# 20260317.net
KiCad netlist of a schematic drawn in EasyEDA Pro
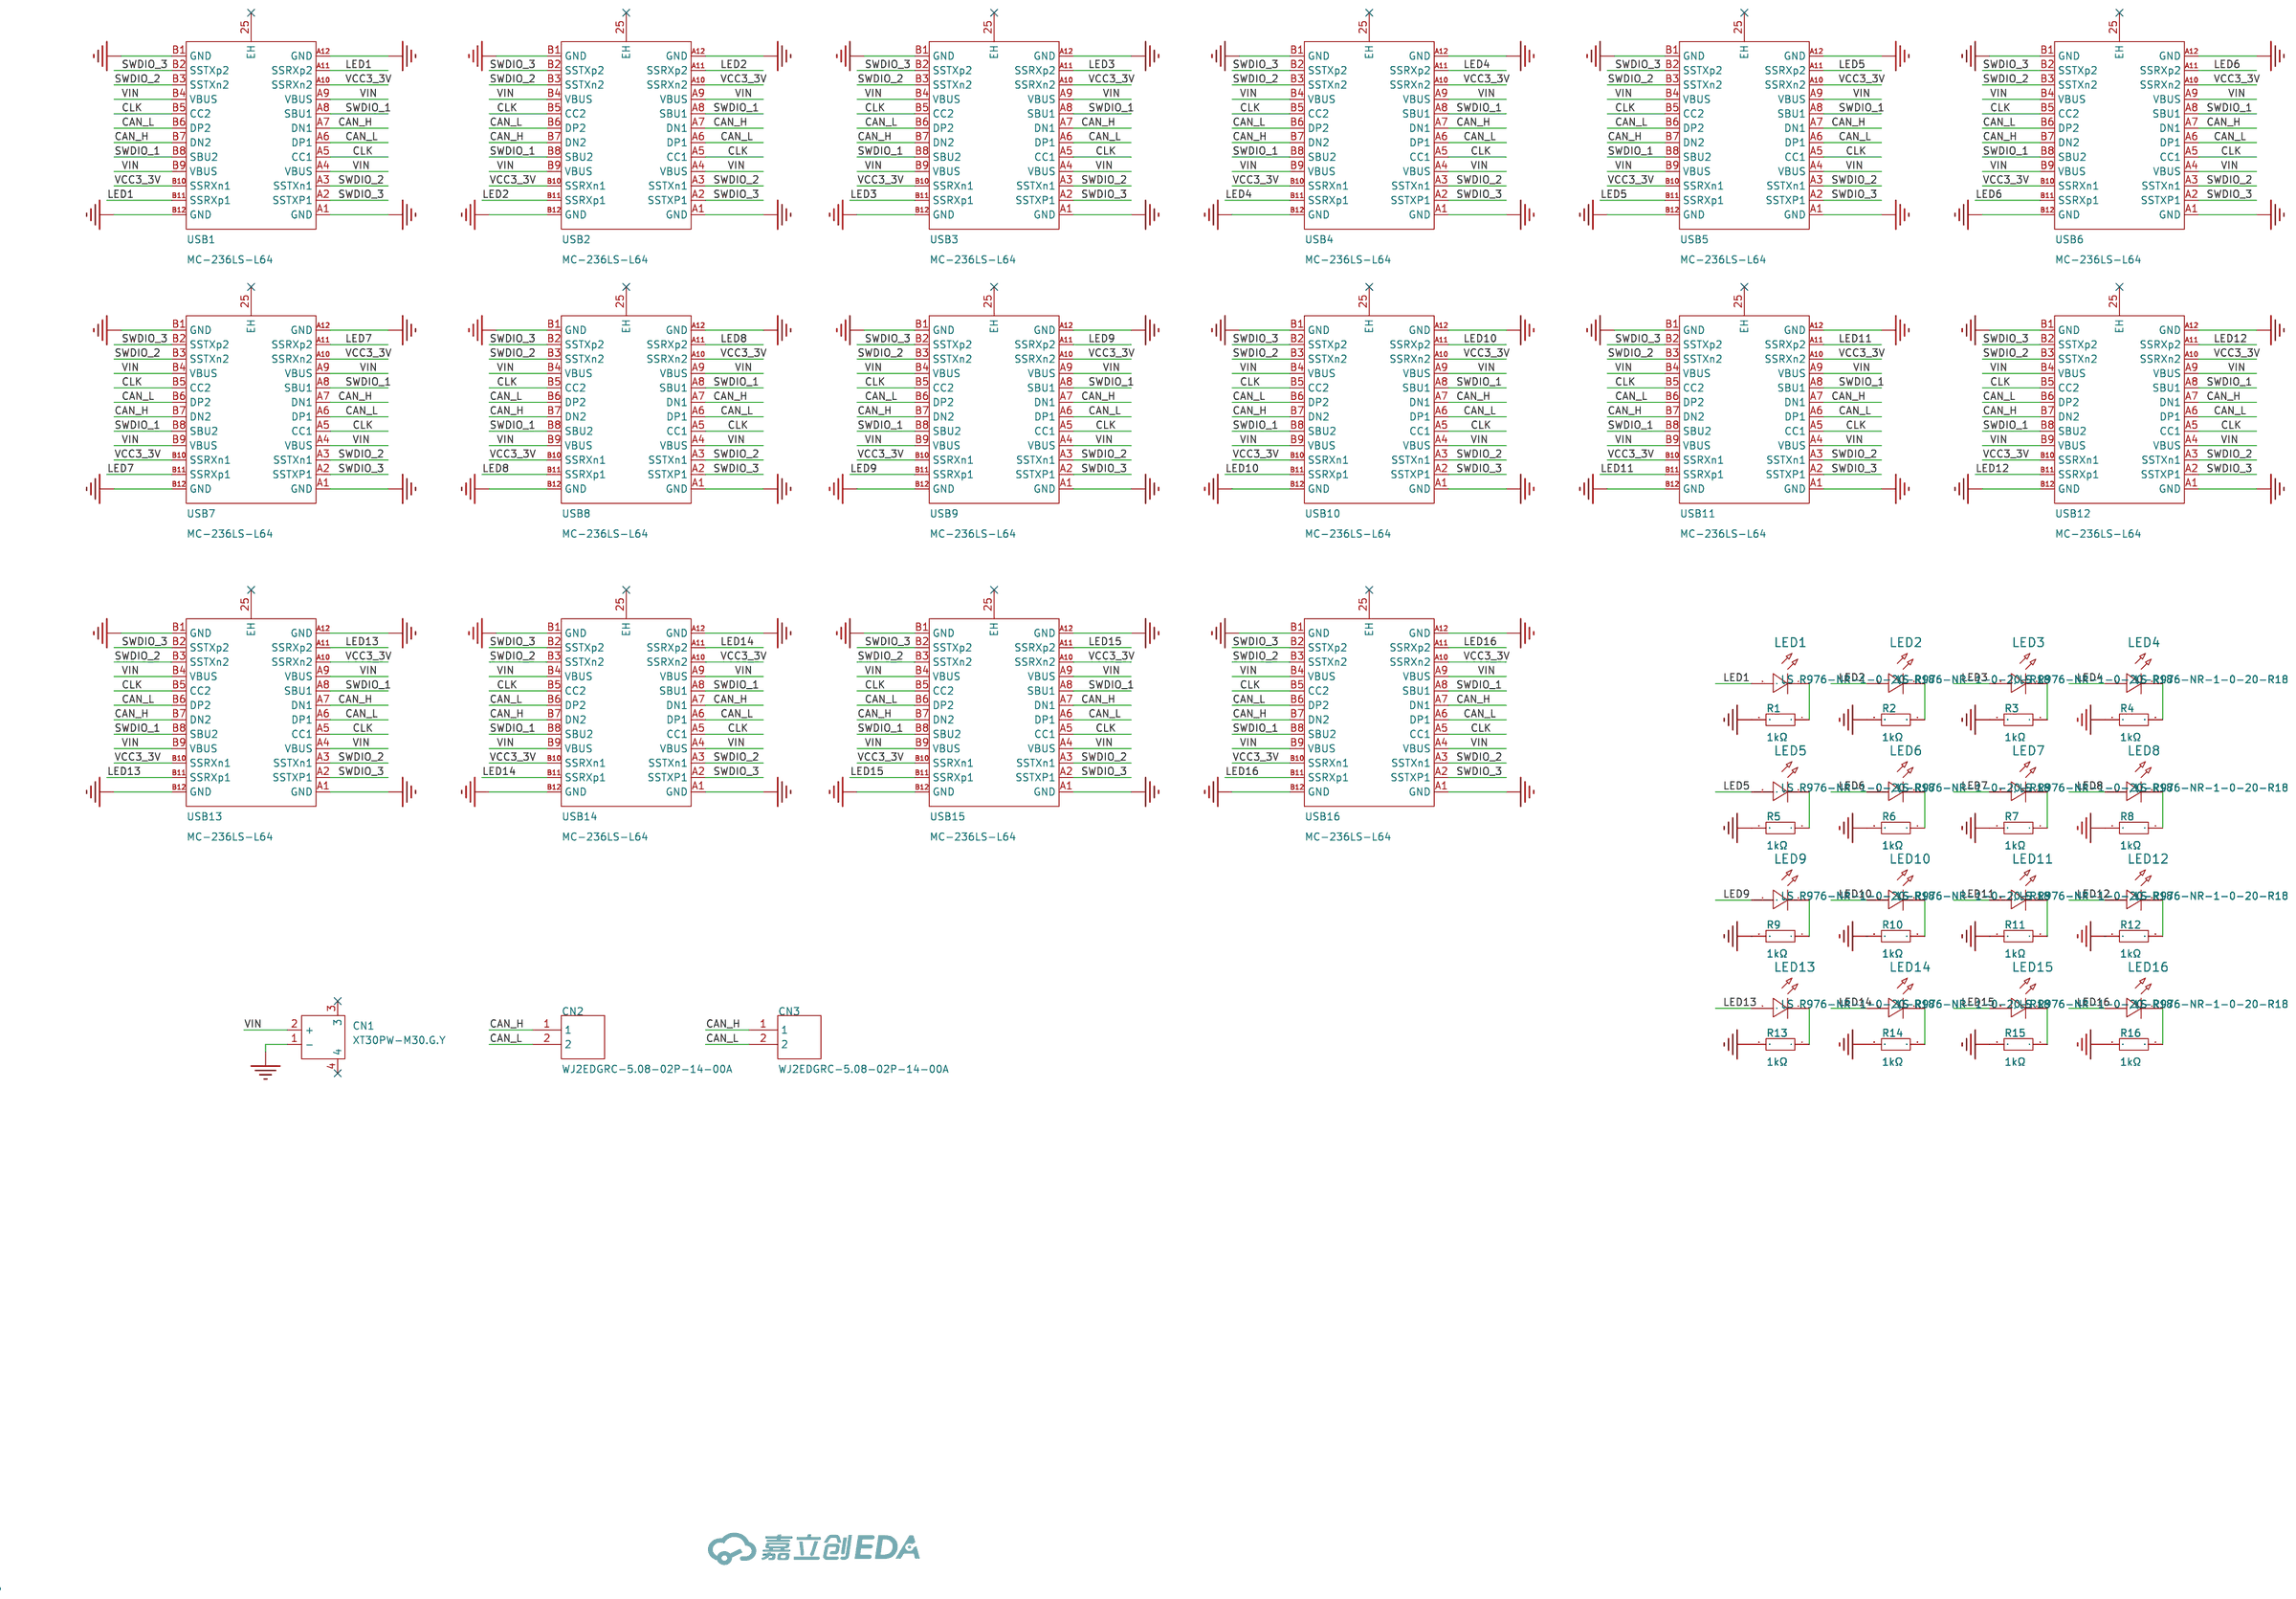
[diagram p0: schematic sheet]

(export (version "E")
  (design (tool "Eeschema 10.0.6"))
  (components
    (comp (ref "CN1")
      (value "XT30PW-M30.G.Y")
      (footprint "easyedapro:CONN-TH_XT30PW-M")
      (description "类别:-;类型1:-;")
      (fields (field (name "Manufacturer") "AMASS(艾迈斯)"))
      (libsource (lib "easyedapro") (part "XT30PW-M"))
    )
    (comp (ref "CN2")
      (value "WJ2EDGRC-5.08-02P-14-00A")
      (footprint "easyedapro:CONN-TH_2P-P5.08_WJ2EDGRC-5.08-2P")
      (fields (field (name "Manufacturer") "KANGNEX(康奈克斯电气)"))
      (libsource (lib "easyedapro") (part "WJ2EDGRC-5.08-2P"))
    )
    (comp (ref "CN3")
      (value "WJ2EDGRC-5.08-02P-14-00A")
      (footprint "easyedapro:CONN-TH_2P-P5.08_WJ2EDGRC-5.08-2P")
      (fields (field (name "Manufacturer") "KANGNEX(康奈克斯电气)"))
      (libsource (lib "easyedapro") (part "WJ2EDGRC-5.08-2P"))
    )
    (comp (ref "LED1")
      (value "LS R976-NR-1-0-20-R18")
      (footprint "easyedapro:LED_0805")
      (fields (field (name "Manufacturer") "OSRAM(欧司朗)"))
      (libsource (lib "easyedapro") (part "LED_R"))
    )
    (comp (ref "LED2")
      (value "LS R976-NR-1-0-20-R18")
      (footprint "easyedapro:LED_0805")
      (fields (field (name "Manufacturer") "OSRAM(欧司朗)"))
      (libsource (lib "easyedapro") (part "LED_R"))
    )
    (comp (ref "LED3")
      (value "LS R976-NR-1-0-20-R18")
      (footprint "easyedapro:LED_0805")
      (fields (field (name "Manufacturer") "OSRAM(欧司朗)"))
      (libsource (lib "easyedapro") (part "LED_R"))
    )
    (comp (ref "LED4")
      (value "LS R976-NR-1-0-20-R18")
      (footprint "easyedapro:LED_0805")
      (fields (field (name "Manufacturer") "OSRAM(欧司朗)"))
      (libsource (lib "easyedapro") (part "LED_R"))
    )
    (comp (ref "LED5")
      (value "LS R976-NR-1-0-20-R18")
      (footprint "easyedapro:LED_0805")
      (fields (field (name "Manufacturer") "OSRAM(欧司朗)"))
      (libsource (lib "easyedapro") (part "LED_R"))
    )
    (comp (ref "LED6")
      (value "LS R976-NR-1-0-20-R18")
      (footprint "easyedapro:LED_0805")
      (fields (field (name "Manufacturer") "OSRAM(欧司朗)"))
      (libsource (lib "easyedapro") (part "LED_R"))
    )
    (comp (ref "LED7")
      (value "LS R976-NR-1-0-20-R18")
      (footprint "easyedapro:LED_0805")
      (fields (field (name "Manufacturer") "OSRAM(欧司朗)"))
      (libsource (lib "easyedapro") (part "LED_R"))
    )
    (comp (ref "LED8")
      (value "LS R976-NR-1-0-20-R18")
      (footprint "easyedapro:LED_0805")
      (fields (field (name "Manufacturer") "OSRAM(欧司朗)"))
      (libsource (lib "easyedapro") (part "LED_R"))
    )
    (comp (ref "LED9")
      (value "LS R976-NR-1-0-20-R18")
      (footprint "easyedapro:LED_0805")
      (fields (field (name "Manufacturer") "OSRAM(欧司朗)"))
      (libsource (lib "easyedapro") (part "LED_R"))
    )
    (comp (ref "LED10")
      (value "LS R976-NR-1-0-20-R18")
      (footprint "easyedapro:LED_0805")
      (fields (field (name "Manufacturer") "OSRAM(欧司朗)"))
      (libsource (lib "easyedapro") (part "LED_R"))
    )
    (comp (ref "LED11")
      (value "LS R976-NR-1-0-20-R18")
      (footprint "easyedapro:LED_0805")
      (fields (field (name "Manufacturer") "OSRAM(欧司朗)"))
      (libsource (lib "easyedapro") (part "LED_R"))
    )
    (comp (ref "LED12")
      (value "LS R976-NR-1-0-20-R18")
      (footprint "easyedapro:LED_0805")
      (fields (field (name "Manufacturer") "OSRAM(欧司朗)"))
      (libsource (lib "easyedapro") (part "LED_R"))
    )
    (comp (ref "LED13")
      (value "LS R976-NR-1-0-20-R18")
      (footprint "easyedapro:LED_0805")
      (fields (field (name "Manufacturer") "OSRAM(欧司朗)"))
      (libsource (lib "easyedapro") (part "LED_R"))
    )
    (comp (ref "LED14")
      (value "LS R976-NR-1-0-20-R18")
      (footprint "easyedapro:LED_0805")
      (fields (field (name "Manufacturer") "OSRAM(欧司朗)"))
      (libsource (lib "easyedapro") (part "LED_R"))
    )
    (comp (ref "LED15")
      (value "LS R976-NR-1-0-20-R18")
      (footprint "easyedapro:LED_0805")
      (fields (field (name "Manufacturer") "OSRAM(欧司朗)"))
      (libsource (lib "easyedapro") (part "LED_R"))
    )
    (comp (ref "LED16")
      (value "LS R976-NR-1-0-20-R18")
      (footprint "easyedapro:LED_0805")
      (fields (field (name "Manufacturer") "OSRAM(欧司朗)"))
      (libsource (lib "easyedapro") (part "LED_R"))
    )
    (comp (ref "R1")
      (value "1kΩ")
      (footprint "easyedapro:R0805")
      (fields
        (field (name "Manufacturer Part") "0805W8F1001T5E")
        (field (name "Manufacturer") "UNI-ROYAL(厚声)")
      )
      (libsource (lib "easyedapro") (part "电阻"))
    )
    (comp (ref "R2")
      (value "1kΩ")
      (footprint "easyedapro:R0805")
      (fields
        (field (name "Manufacturer Part") "0805W8F1001T5E")
        (field (name "Manufacturer") "UNI-ROYAL(厚声)")
      )
      (libsource (lib "easyedapro") (part "电阻"))
    )
    (comp (ref "R3")
      (value "1kΩ")
      (footprint "easyedapro:R0805")
      (fields
        (field (name "Manufacturer Part") "0805W8F1001T5E")
        (field (name "Manufacturer") "UNI-ROYAL(厚声)")
      )
      (libsource (lib "easyedapro") (part "电阻"))
    )
    (comp (ref "R4")
      (value "1kΩ")
      (footprint "easyedapro:R0805")
      (fields
        (field (name "Manufacturer Part") "0805W8F1001T5E")
        (field (name "Manufacturer") "UNI-ROYAL(厚声)")
      )
      (libsource (lib "easyedapro") (part "电阻"))
    )
    (comp (ref "R5")
      (value "1kΩ")
      (footprint "easyedapro:R0805")
      (fields
        (field (name "Manufacturer Part") "0805W8F1001T5E")
        (field (name "Manufacturer") "UNI-ROYAL(厚声)")
      )
      (libsource (lib "easyedapro") (part "电阻"))
    )
    (comp (ref "R6")
      (value "1kΩ")
      (footprint "easyedapro:R0805")
      (fields
        (field (name "Manufacturer Part") "0805W8F1001T5E")
        (field (name "Manufacturer") "UNI-ROYAL(厚声)")
      )
      (libsource (lib "easyedapro") (part "电阻"))
    )
    (comp (ref "R7")
      (value "1kΩ")
      (footprint "easyedapro:R0805")
      (fields
        (field (name "Manufacturer Part") "0805W8F1001T5E")
        (field (name "Manufacturer") "UNI-ROYAL(厚声)")
      )
      (libsource (lib "easyedapro") (part "电阻"))
    )
    (comp (ref "R8")
      (value "1kΩ")
      (footprint "easyedapro:R0805")
      (fields
        (field (name "Manufacturer Part") "0805W8F1001T5E")
        (field (name "Manufacturer") "UNI-ROYAL(厚声)")
      )
      (libsource (lib "easyedapro") (part "电阻"))
    )
    (comp (ref "R9")
      (value "1kΩ")
      (footprint "easyedapro:R0805")
      (fields
        (field (name "Manufacturer Part") "0805W8F1001T5E")
        (field (name "Manufacturer") "UNI-ROYAL(厚声)")
      )
      (libsource (lib "easyedapro") (part "电阻"))
    )
    (comp (ref "R10")
      (value "1kΩ")
      (footprint "easyedapro:R0805")
      (fields
        (field (name "Manufacturer Part") "0805W8F1001T5E")
        (field (name "Manufacturer") "UNI-ROYAL(厚声)")
      )
      (libsource (lib "easyedapro") (part "电阻"))
    )
    (comp (ref "R11")
      (value "1kΩ")
      (footprint "easyedapro:R0805")
      (fields
        (field (name "Manufacturer Part") "0805W8F1001T5E")
        (field (name "Manufacturer") "UNI-ROYAL(厚声)")
      )
      (libsource (lib "easyedapro") (part "电阻"))
    )
    (comp (ref "R12")
      (value "1kΩ")
      (footprint "easyedapro:R0805")
      (fields
        (field (name "Manufacturer Part") "0805W8F1001T5E")
        (field (name "Manufacturer") "UNI-ROYAL(厚声)")
      )
      (libsource (lib "easyedapro") (part "电阻"))
    )
    (comp (ref "R13")
      (value "1kΩ")
      (footprint "easyedapro:R0805")
      (fields
        (field (name "Manufacturer Part") "0805W8F1001T5E")
        (field (name "Manufacturer") "UNI-ROYAL(厚声)")
      )
      (libsource (lib "easyedapro") (part "电阻"))
    )
    (comp (ref "R14")
      (value "1kΩ")
      (footprint "easyedapro:R0805")
      (fields
        (field (name "Manufacturer Part") "0805W8F1001T5E")
        (field (name "Manufacturer") "UNI-ROYAL(厚声)")
      )
      (libsource (lib "easyedapro") (part "电阻"))
    )
    (comp (ref "R15")
      (value "1kΩ")
      (footprint "easyedapro:R0805")
      (fields
        (field (name "Manufacturer Part") "0805W8F1001T5E")
        (field (name "Manufacturer") "UNI-ROYAL(厚声)")
      )
      (libsource (lib "easyedapro") (part "电阻"))
    )
    (comp (ref "R16")
      (value "1kΩ")
      (footprint "easyedapro:R0805")
      (fields
        (field (name "Manufacturer Part") "0805W8F1001T5E")
        (field (name "Manufacturer") "UNI-ROYAL(厚声)")
      )
      (libsource (lib "easyedapro") (part "电阻"))
    )
    (comp (ref "USB1")
      (value "MC-236LS-L64")
      (footprint "easyedapro:TYPE-C-USB-SMD_TYPE-C-31-M-06")
      (description "连接器类型:Type-C;协议标准:USB 3.1;公母:母;安装方式:立贴;触点数量:24P;端口数量:1;额定电流 - 电源:5A;工作温度:-25°C~+85°C;")
      (fields (field (name "Manufacturer") "HANBO(汉博)"))
      (libsource (lib "easyedapro") (part "MC-236LS-L64"))
    )
    (comp (ref "USB2")
      (value "MC-236LS-L64")
      (footprint "easyedapro:TYPE-C-USB-SMD_TYPE-C-31-M-06")
      (description "连接器类型:Type-C;协议标准:USB 3.1;公母:母;安装方式:立贴;触点数量:24P;端口数量:1;额定电流 - 电源:5A;工作温度:-25°C~+85°C;")
      (fields (field (name "Manufacturer") "HANBO(汉博)"))
      (libsource (lib "easyedapro") (part "MC-236LS-L64"))
    )
    (comp (ref "USB3")
      (value "MC-236LS-L64")
      (footprint "easyedapro:TYPE-C-USB-SMD_TYPE-C-31-M-06")
      (description "连接器类型:Type-C;协议标准:USB 3.1;公母:母;安装方式:立贴;触点数量:24P;端口数量:1;额定电流 - 电源:5A;工作温度:-25°C~+85°C;")
      (fields (field (name "Manufacturer") "HANBO(汉博)"))
      (libsource (lib "easyedapro") (part "MC-236LS-L64"))
    )
    (comp (ref "USB4")
      (value "MC-236LS-L64")
      (footprint "easyedapro:TYPE-C-USB-SMD_TYPE-C-31-M-06")
      (description "连接器类型:Type-C;协议标准:USB 3.1;公母:母;安装方式:立贴;触点数量:24P;端口数量:1;额定电流 - 电源:5A;工作温度:-25°C~+85°C;")
      (fields (field (name "Manufacturer") "HANBO(汉博)"))
      (libsource (lib "easyedapro") (part "MC-236LS-L64"))
    )
    (comp (ref "USB5")
      (value "MC-236LS-L64")
      (footprint "easyedapro:TYPE-C-USB-SMD_TYPE-C-31-M-06")
      (description "连接器类型:Type-C;协议标准:USB 3.1;公母:母;安装方式:立贴;触点数量:24P;端口数量:1;额定电流 - 电源:5A;工作温度:-25°C~+85°C;")
      (fields (field (name "Manufacturer") "HANBO(汉博)"))
      (libsource (lib "easyedapro") (part "MC-236LS-L64"))
    )
    (comp (ref "USB6")
      (value "MC-236LS-L64")
      (footprint "easyedapro:TYPE-C-USB-SMD_TYPE-C-31-M-06")
      (description "连接器类型:Type-C;协议标准:USB 3.1;公母:母;安装方式:立贴;触点数量:24P;端口数量:1;额定电流 - 电源:5A;工作温度:-25°C~+85°C;")
      (fields (field (name "Manufacturer") "HANBO(汉博)"))
      (libsource (lib "easyedapro") (part "MC-236LS-L64"))
    )
    (comp (ref "USB7")
      (value "MC-236LS-L64")
      (footprint "easyedapro:TYPE-C-USB-SMD_TYPE-C-31-M-06")
      (description "连接器类型:Type-C;协议标准:USB 3.1;公母:母;安装方式:立贴;触点数量:24P;端口数量:1;额定电流 - 电源:5A;工作温度:-25°C~+85°C;")
      (fields (field (name "Manufacturer") "HANBO(汉博)"))
      (libsource (lib "easyedapro") (part "MC-236LS-L64"))
    )
    (comp (ref "USB8")
      (value "MC-236LS-L64")
      (footprint "easyedapro:TYPE-C-USB-SMD_TYPE-C-31-M-06")
      (description "连接器类型:Type-C;协议标准:USB 3.1;公母:母;安装方式:立贴;触点数量:24P;端口数量:1;额定电流 - 电源:5A;工作温度:-25°C~+85°C;")
      (fields (field (name "Manufacturer") "HANBO(汉博)"))
      (libsource (lib "easyedapro") (part "MC-236LS-L64"))
    )
    (comp (ref "USB9")
      (value "MC-236LS-L64")
      (footprint "easyedapro:TYPE-C-USB-SMD_TYPE-C-31-M-06")
      (description "连接器类型:Type-C;协议标准:USB 3.1;公母:母;安装方式:立贴;触点数量:24P;端口数量:1;额定电流 - 电源:5A;工作温度:-25°C~+85°C;")
      (fields (field (name "Manufacturer") "HANBO(汉博)"))
      (libsource (lib "easyedapro") (part "MC-236LS-L64"))
    )
    (comp (ref "USB10")
      (value "MC-236LS-L64")
      (footprint "easyedapro:TYPE-C-USB-SMD_TYPE-C-31-M-06")
      (description "连接器类型:Type-C;协议标准:USB 3.1;公母:母;安装方式:立贴;触点数量:24P;端口数量:1;额定电流 - 电源:5A;工作温度:-25°C~+85°C;")
      (fields (field (name "Manufacturer") "HANBO(汉博)"))
      (libsource (lib "easyedapro") (part "MC-236LS-L64"))
    )
    (comp (ref "USB11")
      (value "MC-236LS-L64")
      (footprint "easyedapro:TYPE-C-USB-SMD_TYPE-C-31-M-06")
      (description "连接器类型:Type-C;协议标准:USB 3.1;公母:母;安装方式:立贴;触点数量:24P;端口数量:1;额定电流 - 电源:5A;工作温度:-25°C~+85°C;")
      (fields (field (name "Manufacturer") "HANBO(汉博)"))
      (libsource (lib "easyedapro") (part "MC-236LS-L64"))
    )
    (comp (ref "USB12")
      (value "MC-236LS-L64")
      (footprint "easyedapro:TYPE-C-USB-SMD_TYPE-C-31-M-06")
      (description "连接器类型:Type-C;协议标准:USB 3.1;公母:母;安装方式:立贴;触点数量:24P;端口数量:1;额定电流 - 电源:5A;工作温度:-25°C~+85°C;")
      (fields (field (name "Manufacturer") "HANBO(汉博)"))
      (libsource (lib "easyedapro") (part "MC-236LS-L64"))
    )
    (comp (ref "USB13")
      (value "MC-236LS-L64")
      (footprint "easyedapro:TYPE-C-USB-SMD_TYPE-C-31-M-06")
      (description "连接器类型:Type-C;协议标准:USB 3.1;公母:母;安装方式:立贴;触点数量:24P;端口数量:1;额定电流 - 电源:5A;工作温度:-25°C~+85°C;")
      (fields (field (name "Manufacturer") "HANBO(汉博)"))
      (libsource (lib "easyedapro") (part "MC-236LS-L64"))
    )
    (comp (ref "USB14")
      (value "MC-236LS-L64")
      (footprint "easyedapro:TYPE-C-USB-SMD_TYPE-C-31-M-06")
      (description "连接器类型:Type-C;协议标准:USB 3.1;公母:母;安装方式:立贴;触点数量:24P;端口数量:1;额定电流 - 电源:5A;工作温度:-25°C~+85°C;")
      (fields (field (name "Manufacturer") "HANBO(汉博)"))
      (libsource (lib "easyedapro") (part "MC-236LS-L64"))
    )
    (comp (ref "USB15")
      (value "MC-236LS-L64")
      (footprint "easyedapro:TYPE-C-USB-SMD_TYPE-C-31-M-06")
      (description "连接器类型:Type-C;协议标准:USB 3.1;公母:母;安装方式:立贴;触点数量:24P;端口数量:1;额定电流 - 电源:5A;工作温度:-25°C~+85°C;")
      (fields (field (name "Manufacturer") "HANBO(汉博)"))
      (libsource (lib "easyedapro") (part "MC-236LS-L64"))
    )
    (comp (ref "USB16")
      (value "MC-236LS-L64")
      (footprint "easyedapro:TYPE-C-USB-SMD_TYPE-C-31-M-06")
      (description "连接器类型:Type-C;协议标准:USB 3.1;公母:母;安装方式:立贴;触点数量:24P;端口数量:1;额定电流 - 电源:5A;工作温度:-25°C~+85°C;")
      (fields (field (name "Manufacturer") "HANBO(汉博)"))
      (libsource (lib "easyedapro") (part "MC-236LS-L64"))
    )
  )
  (nets
    (net (code "1") (name "/CAN_H") (class "Default")
      (node (ref "CN2") (pin "1") (pinfunction "1_1") (pintype "unspecified"))
      (node (ref "CN3") (pin "1") (pinfunction "1_1") (pintype "unspecified"))
      (node (ref "USB1") (pin "A7") (pinfunction "DN1_A7") (pintype "unspecified"))
      (node (ref "USB1") (pin "B7") (pinfunction "DN2_B7") (pintype "unspecified"))
      (node (ref "USB10") (pin "A7") (pinfunction "DN1_A7") (pintype "unspecified"))
      (node (ref "USB10") (pin "B7") (pinfunction "DN2_B7") (pintype "unspecified"))
      (node (ref "USB11") (pin "A7") (pinfunction "DN1_A7") (pintype "unspecified"))
      (node (ref "USB11") (pin "B7") (pinfunction "DN2_B7") (pintype "unspecified"))
      (node (ref "USB12") (pin "A7") (pinfunction "DN1_A7") (pintype "unspecified"))
      (node (ref "USB12") (pin "B7") (pinfunction "DN2_B7") (pintype "unspecified"))
      (node (ref "USB13") (pin "A7") (pinfunction "DN1_A7") (pintype "unspecified"))
      (node (ref "USB13") (pin "B7") (pinfunction "DN2_B7") (pintype "unspecified"))
      (node (ref "USB14") (pin "A7") (pinfunction "DN1_A7") (pintype "unspecified"))
      (node (ref "USB14") (pin "B7") (pinfunction "DN2_B7") (pintype "unspecified"))
      (node (ref "USB15") (pin "A7") (pinfunction "DN1_A7") (pintype "unspecified"))
      (node (ref "USB15") (pin "B7") (pinfunction "DN2_B7") (pintype "unspecified"))
      (node (ref "USB16") (pin "A7") (pinfunction "DN1_A7") (pintype "unspecified"))
      (node (ref "USB16") (pin "B7") (pinfunction "DN2_B7") (pintype "unspecified"))
      (node (ref "USB2") (pin "A7") (pinfunction "DN1_A7") (pintype "unspecified"))
      (node (ref "USB2") (pin "B7") (pinfunction "DN2_B7") (pintype "unspecified"))
      (node (ref "USB3") (pin "A7") (pinfunction "DN1_A7") (pintype "unspecified"))
      (node (ref "USB3") (pin "B7") (pinfunction "DN2_B7") (pintype "unspecified"))
      (node (ref "USB4") (pin "A7") (pinfunction "DN1_A7") (pintype "unspecified"))
      (node (ref "USB4") (pin "B7") (pinfunction "DN2_B7") (pintype "unspecified"))
      (node (ref "USB5") (pin "A7") (pinfunction "DN1_A7") (pintype "unspecified"))
      (node (ref "USB5") (pin "B7") (pinfunction "DN2_B7") (pintype "unspecified"))
      (node (ref "USB6") (pin "A7") (pinfunction "DN1_A7") (pintype "unspecified"))
      (node (ref "USB6") (pin "B7") (pinfunction "DN2_B7") (pintype "unspecified"))
      (node (ref "USB7") (pin "A7") (pinfunction "DN1_A7") (pintype "unspecified"))
      (node (ref "USB7") (pin "B7") (pinfunction "DN2_B7") (pintype "unspecified"))
      (node (ref "USB8") (pin "A7") (pinfunction "DN1_A7") (pintype "unspecified"))
      (node (ref "USB8") (pin "B7") (pinfunction "DN2_B7") (pintype "unspecified"))
      (node (ref "USB9") (pin "A7") (pinfunction "DN1_A7") (pintype "unspecified"))
      (node (ref "USB9") (pin "B7") (pinfunction "DN2_B7") (pintype "unspecified"))
    )
    (net (code "2") (name "/CAN_L") (class "Default")
      (node (ref "CN2") (pin "2") (pinfunction "2_2") (pintype "unspecified"))
      (node (ref "CN3") (pin "2") (pinfunction "2_2") (pintype "unspecified"))
      (node (ref "USB1") (pin "A6") (pinfunction "DP1_A6") (pintype "unspecified"))
      (node (ref "USB1") (pin "B6") (pinfunction "DP2_B6") (pintype "unspecified"))
      (node (ref "USB10") (pin "A6") (pinfunction "DP1_A6") (pintype "unspecified"))
      (node (ref "USB10") (pin "B6") (pinfunction "DP2_B6") (pintype "unspecified"))
      (node (ref "USB11") (pin "A6") (pinfunction "DP1_A6") (pintype "unspecified"))
      (node (ref "USB11") (pin "B6") (pinfunction "DP2_B6") (pintype "unspecified"))
      (node (ref "USB12") (pin "A6") (pinfunction "DP1_A6") (pintype "unspecified"))
      (node (ref "USB12") (pin "B6") (pinfunction "DP2_B6") (pintype "unspecified"))
      (node (ref "USB13") (pin "A6") (pinfunction "DP1_A6") (pintype "unspecified"))
      (node (ref "USB13") (pin "B6") (pinfunction "DP2_B6") (pintype "unspecified"))
      (node (ref "USB14") (pin "A6") (pinfunction "DP1_A6") (pintype "unspecified"))
      (node (ref "USB14") (pin "B6") (pinfunction "DP2_B6") (pintype "unspecified"))
      (node (ref "USB15") (pin "A6") (pinfunction "DP1_A6") (pintype "unspecified"))
      (node (ref "USB15") (pin "B6") (pinfunction "DP2_B6") (pintype "unspecified"))
      (node (ref "USB16") (pin "A6") (pinfunction "DP1_A6") (pintype "unspecified"))
      (node (ref "USB16") (pin "B6") (pinfunction "DP2_B6") (pintype "unspecified"))
      (node (ref "USB2") (pin "A6") (pinfunction "DP1_A6") (pintype "unspecified"))
      (node (ref "USB2") (pin "B6") (pinfunction "DP2_B6") (pintype "unspecified"))
      (node (ref "USB3") (pin "A6") (pinfunction "DP1_A6") (pintype "unspecified"))
      (node (ref "USB3") (pin "B6") (pinfunction "DP2_B6") (pintype "unspecified"))
      (node (ref "USB4") (pin "A6") (pinfunction "DP1_A6") (pintype "unspecified"))
      (node (ref "USB4") (pin "B6") (pinfunction "DP2_B6") (pintype "unspecified"))
      (node (ref "USB5") (pin "A6") (pinfunction "DP1_A6") (pintype "unspecified"))
      (node (ref "USB5") (pin "B6") (pinfunction "DP2_B6") (pintype "unspecified"))
      (node (ref "USB6") (pin "A6") (pinfunction "DP1_A6") (pintype "unspecified"))
      (node (ref "USB6") (pin "B6") (pinfunction "DP2_B6") (pintype "unspecified"))
      (node (ref "USB7") (pin "A6") (pinfunction "DP1_A6") (pintype "unspecified"))
      (node (ref "USB7") (pin "B6") (pinfunction "DP2_B6") (pintype "unspecified"))
      (node (ref "USB8") (pin "A6") (pinfunction "DP1_A6") (pintype "unspecified"))
      (node (ref "USB8") (pin "B6") (pinfunction "DP2_B6") (pintype "unspecified"))
      (node (ref "USB9") (pin "A6") (pinfunction "DP1_A6") (pintype "unspecified"))
      (node (ref "USB9") (pin "B6") (pinfunction "DP2_B6") (pintype "unspecified"))
    )
    (net (code "3") (name "/CLK") (class "Default")
      (node (ref "USB1") (pin "A5") (pinfunction "CC1_A5") (pintype "unspecified"))
      (node (ref "USB1") (pin "B5") (pinfunction "CC2_B5") (pintype "unspecified"))
      (node (ref "USB10") (pin "A5") (pinfunction "CC1_A5") (pintype "unspecified"))
      (node (ref "USB10") (pin "B5") (pinfunction "CC2_B5") (pintype "unspecified"))
      (node (ref "USB11") (pin "A5") (pinfunction "CC1_A5") (pintype "unspecified"))
      (node (ref "USB11") (pin "B5") (pinfunction "CC2_B5") (pintype "unspecified"))
      (node (ref "USB12") (pin "A5") (pinfunction "CC1_A5") (pintype "unspecified"))
      (node (ref "USB12") (pin "B5") (pinfunction "CC2_B5") (pintype "unspecified"))
      (node (ref "USB13") (pin "A5") (pinfunction "CC1_A5") (pintype "unspecified"))
      (node (ref "USB13") (pin "B5") (pinfunction "CC2_B5") (pintype "unspecified"))
      (node (ref "USB14") (pin "A5") (pinfunction "CC1_A5") (pintype "unspecified"))
      (node (ref "USB14") (pin "B5") (pinfunction "CC2_B5") (pintype "unspecified"))
      (node (ref "USB15") (pin "A5") (pinfunction "CC1_A5") (pintype "unspecified"))
      (node (ref "USB15") (pin "B5") (pinfunction "CC2_B5") (pintype "unspecified"))
      (node (ref "USB16") (pin "A5") (pinfunction "CC1_A5") (pintype "unspecified"))
      (node (ref "USB16") (pin "B5") (pinfunction "CC2_B5") (pintype "unspecified"))
      (node (ref "USB2") (pin "A5") (pinfunction "CC1_A5") (pintype "unspecified"))
      (node (ref "USB2") (pin "B5") (pinfunction "CC2_B5") (pintype "unspecified"))
      (node (ref "USB3") (pin "A5") (pinfunction "CC1_A5") (pintype "unspecified"))
      (node (ref "USB3") (pin "B5") (pinfunction "CC2_B5") (pintype "unspecified"))
      (node (ref "USB4") (pin "A5") (pinfunction "CC1_A5") (pintype "unspecified"))
      (node (ref "USB4") (pin "B5") (pinfunction "CC2_B5") (pintype "unspecified"))
      (node (ref "USB5") (pin "A5") (pinfunction "CC1_A5") (pintype "unspecified"))
      (node (ref "USB5") (pin "B5") (pinfunction "CC2_B5") (pintype "unspecified"))
      (node (ref "USB6") (pin "A5") (pinfunction "CC1_A5") (pintype "unspecified"))
      (node (ref "USB6") (pin "B5") (pinfunction "CC2_B5") (pintype "unspecified"))
      (node (ref "USB7") (pin "A5") (pinfunction "CC1_A5") (pintype "unspecified"))
      (node (ref "USB7") (pin "B5") (pinfunction "CC2_B5") (pintype "unspecified"))
      (node (ref "USB8") (pin "A5") (pinfunction "CC1_A5") (pintype "unspecified"))
      (node (ref "USB8") (pin "B5") (pinfunction "CC2_B5") (pintype "unspecified"))
      (node (ref "USB9") (pin "A5") (pinfunction "CC1_A5") (pintype "unspecified"))
      (node (ref "USB9") (pin "B5") (pinfunction "CC2_B5") (pintype "unspecified"))
    )
    (net (code "4") (name "/LED1") (class "Default")
      (node (ref "LED1") (pin "2") (pinfunction "A_2") (pintype "input"))
      (node (ref "USB1") (pin "A11") (pinfunction "SSRXp2_A11") (pintype "unspecified"))
      (node (ref "USB1") (pin "B11") (pinfunction "SSRXp1_B11") (pintype "unspecified"))
    )
    (net (code "5") (name "/LED2") (class "Default")
      (node (ref "LED2") (pin "2") (pinfunction "A_2") (pintype "input"))
      (node (ref "USB2") (pin "A11") (pinfunction "SSRXp2_A11") (pintype "unspecified"))
      (node (ref "USB2") (pin "B11") (pinfunction "SSRXp1_B11") (pintype "unspecified"))
    )
    (net (code "6") (name "/LED3") (class "Default")
      (node (ref "LED3") (pin "2") (pinfunction "A_2") (pintype "input"))
      (node (ref "USB3") (pin "A11") (pinfunction "SSRXp2_A11") (pintype "unspecified"))
      (node (ref "USB3") (pin "B11") (pinfunction "SSRXp1_B11") (pintype "unspecified"))
    )
    (net (code "7") (name "/LED4") (class "Default")
      (node (ref "LED4") (pin "2") (pinfunction "A_2") (pintype "input"))
      (node (ref "USB4") (pin "A11") (pinfunction "SSRXp2_A11") (pintype "unspecified"))
      (node (ref "USB4") (pin "B11") (pinfunction "SSRXp1_B11") (pintype "unspecified"))
    )
    (net (code "8") (name "/LED5") (class "Default")
      (node (ref "LED5") (pin "2") (pinfunction "A_2") (pintype "input"))
      (node (ref "USB5") (pin "A11") (pinfunction "SSRXp2_A11") (pintype "unspecified"))
      (node (ref "USB5") (pin "B11") (pinfunction "SSRXp1_B11") (pintype "unspecified"))
    )
    (net (code "9") (name "/LED6") (class "Default")
      (node (ref "LED6") (pin "2") (pinfunction "A_2") (pintype "input"))
      (node (ref "USB6") (pin "A11") (pinfunction "SSRXp2_A11") (pintype "unspecified"))
      (node (ref "USB6") (pin "B11") (pinfunction "SSRXp1_B11") (pintype "unspecified"))
    )
    (net (code "10") (name "/LED7") (class "Default")
      (node (ref "LED7") (pin "2") (pinfunction "A_2") (pintype "input"))
      (node (ref "USB7") (pin "A11") (pinfunction "SSRXp2_A11") (pintype "unspecified"))
      (node (ref "USB7") (pin "B11") (pinfunction "SSRXp1_B11") (pintype "unspecified"))
    )
    (net (code "11") (name "/LED8") (class "Default")
      (node (ref "LED8") (pin "2") (pinfunction "A_2") (pintype "input"))
      (node (ref "USB8") (pin "A11") (pinfunction "SSRXp2_A11") (pintype "unspecified"))
      (node (ref "USB8") (pin "B11") (pinfunction "SSRXp1_B11") (pintype "unspecified"))
    )
    (net (code "12") (name "/LED9") (class "Default")
      (node (ref "LED9") (pin "2") (pinfunction "A_2") (pintype "input"))
      (node (ref "USB9") (pin "A11") (pinfunction "SSRXp2_A11") (pintype "unspecified"))
      (node (ref "USB9") (pin "B11") (pinfunction "SSRXp1_B11") (pintype "unspecified"))
    )
    (net (code "13") (name "/LED10") (class "Default")
      (node (ref "LED10") (pin "2") (pinfunction "A_2") (pintype "input"))
      (node (ref "USB10") (pin "A11") (pinfunction "SSRXp2_A11") (pintype "unspecified"))
      (node (ref "USB10") (pin "B11") (pinfunction "SSRXp1_B11") (pintype "unspecified"))
    )
    (net (code "14") (name "/LED11") (class "Default")
      (node (ref "LED11") (pin "2") (pinfunction "A_2") (pintype "input"))
      (node (ref "USB11") (pin "A11") (pinfunction "SSRXp2_A11") (pintype "unspecified"))
      (node (ref "USB11") (pin "B11") (pinfunction "SSRXp1_B11") (pintype "unspecified"))
    )
    (net (code "15") (name "/LED12") (class "Default")
      (node (ref "LED12") (pin "2") (pinfunction "A_2") (pintype "input"))
      (node (ref "USB12") (pin "A11") (pinfunction "SSRXp2_A11") (pintype "unspecified"))
      (node (ref "USB12") (pin "B11") (pinfunction "SSRXp1_B11") (pintype "unspecified"))
    )
    (net (code "16") (name "/LED13") (class "Default")
      (node (ref "LED13") (pin "2") (pinfunction "A_2") (pintype "input"))
      (node (ref "USB13") (pin "A11") (pinfunction "SSRXp2_A11") (pintype "unspecified"))
      (node (ref "USB13") (pin "B11") (pinfunction "SSRXp1_B11") (pintype "unspecified"))
    )
    (net (code "17") (name "/LED14") (class "Default")
      (node (ref "LED14") (pin "2") (pinfunction "A_2") (pintype "input"))
      (node (ref "USB14") (pin "A11") (pinfunction "SSRXp2_A11") (pintype "unspecified"))
      (node (ref "USB14") (pin "B11") (pinfunction "SSRXp1_B11") (pintype "unspecified"))
    )
    (net (code "18") (name "/LED15") (class "Default")
      (node (ref "LED15") (pin "2") (pinfunction "A_2") (pintype "input"))
      (node (ref "USB15") (pin "A11") (pinfunction "SSRXp2_A11") (pintype "unspecified"))
      (node (ref "USB15") (pin "B11") (pinfunction "SSRXp1_B11") (pintype "unspecified"))
    )
    (net (code "19") (name "/LED16") (class "Default")
      (node (ref "LED16") (pin "2") (pinfunction "A_2") (pintype "input"))
      (node (ref "USB16") (pin "A11") (pinfunction "SSRXp2_A11") (pintype "unspecified"))
      (node (ref "USB16") (pin "B11") (pinfunction "SSRXp1_B11") (pintype "unspecified"))
    )
    (net (code "20") (name "/SWDIO_1") (class "Default")
      (node (ref "USB1") (pin "A8") (pinfunction "SBU1_A8") (pintype "unspecified"))
      (node (ref "USB1") (pin "B8") (pinfunction "SBU2_B8") (pintype "unspecified"))
      (node (ref "USB10") (pin "A8") (pinfunction "SBU1_A8") (pintype "unspecified"))
      (node (ref "USB10") (pin "B8") (pinfunction "SBU2_B8") (pintype "unspecified"))
      (node (ref "USB11") (pin "A8") (pinfunction "SBU1_A8") (pintype "unspecified"))
      (node (ref "USB11") (pin "B8") (pinfunction "SBU2_B8") (pintype "unspecified"))
      (node (ref "USB12") (pin "A8") (pinfunction "SBU1_A8") (pintype "unspecified"))
      (node (ref "USB12") (pin "B8") (pinfunction "SBU2_B8") (pintype "unspecified"))
      (node (ref "USB13") (pin "A8") (pinfunction "SBU1_A8") (pintype "unspecified"))
      (node (ref "USB13") (pin "B8") (pinfunction "SBU2_B8") (pintype "unspecified"))
      (node (ref "USB14") (pin "A8") (pinfunction "SBU1_A8") (pintype "unspecified"))
      (node (ref "USB14") (pin "B8") (pinfunction "SBU2_B8") (pintype "unspecified"))
      (node (ref "USB15") (pin "A8") (pinfunction "SBU1_A8") (pintype "unspecified"))
      (node (ref "USB15") (pin "B8") (pinfunction "SBU2_B8") (pintype "unspecified"))
      (node (ref "USB16") (pin "A8") (pinfunction "SBU1_A8") (pintype "unspecified"))
      (node (ref "USB16") (pin "B8") (pinfunction "SBU2_B8") (pintype "unspecified"))
      (node (ref "USB2") (pin "A8") (pinfunction "SBU1_A8") (pintype "unspecified"))
      (node (ref "USB2") (pin "B8") (pinfunction "SBU2_B8") (pintype "unspecified"))
      (node (ref "USB3") (pin "A8") (pinfunction "SBU1_A8") (pintype "unspecified"))
      (node (ref "USB3") (pin "B8") (pinfunction "SBU2_B8") (pintype "unspecified"))
      (node (ref "USB4") (pin "A8") (pinfunction "SBU1_A8") (pintype "unspecified"))
      (node (ref "USB4") (pin "B8") (pinfunction "SBU2_B8") (pintype "unspecified"))
      (node (ref "USB5") (pin "A8") (pinfunction "SBU1_A8") (pintype "unspecified"))
      (node (ref "USB5") (pin "B8") (pinfunction "SBU2_B8") (pintype "unspecified"))
      (node (ref "USB6") (pin "A8") (pinfunction "SBU1_A8") (pintype "unspecified"))
      (node (ref "USB6") (pin "B8") (pinfunction "SBU2_B8") (pintype "unspecified"))
      (node (ref "USB7") (pin "A8") (pinfunction "SBU1_A8") (pintype "unspecified"))
      (node (ref "USB7") (pin "B8") (pinfunction "SBU2_B8") (pintype "unspecified"))
      (node (ref "USB8") (pin "A8") (pinfunction "SBU1_A8") (pintype "unspecified"))
      (node (ref "USB8") (pin "B8") (pinfunction "SBU2_B8") (pintype "unspecified"))
      (node (ref "USB9") (pin "A8") (pinfunction "SBU1_A8") (pintype "unspecified"))
      (node (ref "USB9") (pin "B8") (pinfunction "SBU2_B8") (pintype "unspecified"))
    )
    (net (code "21") (name "/SWDIO_2") (class "Default")
      (node (ref "USB1") (pin "A3") (pinfunction "SSTXn1_A3") (pintype "unspecified"))
      (node (ref "USB1") (pin "B3") (pinfunction "SSTXn2_B3") (pintype "unspecified"))
      (node (ref "USB10") (pin "A3") (pinfunction "SSTXn1_A3") (pintype "unspecified"))
      (node (ref "USB10") (pin "B3") (pinfunction "SSTXn2_B3") (pintype "unspecified"))
      (node (ref "USB11") (pin "A3") (pinfunction "SSTXn1_A3") (pintype "unspecified"))
      (node (ref "USB11") (pin "B3") (pinfunction "SSTXn2_B3") (pintype "unspecified"))
      (node (ref "USB12") (pin "A3") (pinfunction "SSTXn1_A3") (pintype "unspecified"))
      (node (ref "USB12") (pin "B3") (pinfunction "SSTXn2_B3") (pintype "unspecified"))
      (node (ref "USB13") (pin "A3") (pinfunction "SSTXn1_A3") (pintype "unspecified"))
      (node (ref "USB13") (pin "B3") (pinfunction "SSTXn2_B3") (pintype "unspecified"))
      (node (ref "USB14") (pin "A3") (pinfunction "SSTXn1_A3") (pintype "unspecified"))
      (node (ref "USB14") (pin "B3") (pinfunction "SSTXn2_B3") (pintype "unspecified"))
      (node (ref "USB15") (pin "A3") (pinfunction "SSTXn1_A3") (pintype "unspecified"))
      (node (ref "USB15") (pin "B3") (pinfunction "SSTXn2_B3") (pintype "unspecified"))
      (node (ref "USB16") (pin "A3") (pinfunction "SSTXn1_A3") (pintype "unspecified"))
      (node (ref "USB16") (pin "B3") (pinfunction "SSTXn2_B3") (pintype "unspecified"))
      (node (ref "USB2") (pin "A3") (pinfunction "SSTXn1_A3") (pintype "unspecified"))
      (node (ref "USB2") (pin "B3") (pinfunction "SSTXn2_B3") (pintype "unspecified"))
      (node (ref "USB3") (pin "A3") (pinfunction "SSTXn1_A3") (pintype "unspecified"))
      (node (ref "USB3") (pin "B3") (pinfunction "SSTXn2_B3") (pintype "unspecified"))
      (node (ref "USB4") (pin "A3") (pinfunction "SSTXn1_A3") (pintype "unspecified"))
      (node (ref "USB4") (pin "B3") (pinfunction "SSTXn2_B3") (pintype "unspecified"))
      (node (ref "USB5") (pin "A3") (pinfunction "SSTXn1_A3") (pintype "unspecified"))
      (node (ref "USB5") (pin "B3") (pinfunction "SSTXn2_B3") (pintype "unspecified"))
      (node (ref "USB6") (pin "A3") (pinfunction "SSTXn1_A3") (pintype "unspecified"))
      (node (ref "USB6") (pin "B3") (pinfunction "SSTXn2_B3") (pintype "unspecified"))
      (node (ref "USB7") (pin "A3") (pinfunction "SSTXn1_A3") (pintype "unspecified"))
      (node (ref "USB7") (pin "B3") (pinfunction "SSTXn2_B3") (pintype "unspecified"))
      (node (ref "USB8") (pin "A3") (pinfunction "SSTXn1_A3") (pintype "unspecified"))
      (node (ref "USB8") (pin "B3") (pinfunction "SSTXn2_B3") (pintype "unspecified"))
      (node (ref "USB9") (pin "A3") (pinfunction "SSTXn1_A3") (pintype "unspecified"))
      (node (ref "USB9") (pin "B3") (pinfunction "SSTXn2_B3") (pintype "unspecified"))
    )
    (net (code "22") (name "/SWDIO_3") (class "Default")
      (node (ref "USB1") (pin "A2") (pinfunction "SSTXP1_A2") (pintype "unspecified"))
      (node (ref "USB1") (pin "B2") (pinfunction "SSTXp2_B2") (pintype "unspecified"))
      (node (ref "USB10") (pin "A2") (pinfunction "SSTXP1_A2") (pintype "unspecified"))
      (node (ref "USB10") (pin "B2") (pinfunction "SSTXp2_B2") (pintype "unspecified"))
      (node (ref "USB11") (pin "A2") (pinfunction "SSTXP1_A2") (pintype "unspecified"))
      (node (ref "USB11") (pin "B2") (pinfunction "SSTXp2_B2") (pintype "unspecified"))
      (node (ref "USB12") (pin "A2") (pinfunction "SSTXP1_A2") (pintype "unspecified"))
      (node (ref "USB12") (pin "B2") (pinfunction "SSTXp2_B2") (pintype "unspecified"))
      (node (ref "USB13") (pin "A2") (pinfunction "SSTXP1_A2") (pintype "unspecified"))
      (node (ref "USB13") (pin "B2") (pinfunction "SSTXp2_B2") (pintype "unspecified"))
      (node (ref "USB14") (pin "A2") (pinfunction "SSTXP1_A2") (pintype "unspecified"))
      (node (ref "USB14") (pin "B2") (pinfunction "SSTXp2_B2") (pintype "unspecified"))
      (node (ref "USB15") (pin "A2") (pinfunction "SSTXP1_A2") (pintype "unspecified"))
      (node (ref "USB15") (pin "B2") (pinfunction "SSTXp2_B2") (pintype "unspecified"))
      (node (ref "USB16") (pin "A2") (pinfunction "SSTXP1_A2") (pintype "unspecified"))
      (node (ref "USB16") (pin "B2") (pinfunction "SSTXp2_B2") (pintype "unspecified"))
      (node (ref "USB2") (pin "A2") (pinfunction "SSTXP1_A2") (pintype "unspecified"))
      (node (ref "USB2") (pin "B2") (pinfunction "SSTXp2_B2") (pintype "unspecified"))
      (node (ref "USB3") (pin "A2") (pinfunction "SSTXP1_A2") (pintype "unspecified"))
      (node (ref "USB3") (pin "B2") (pinfunction "SSTXp2_B2") (pintype "unspecified"))
      (node (ref "USB4") (pin "A2") (pinfunction "SSTXP1_A2") (pintype "unspecified"))
      (node (ref "USB4") (pin "B2") (pinfunction "SSTXp2_B2") (pintype "unspecified"))
      (node (ref "USB5") (pin "A2") (pinfunction "SSTXP1_A2") (pintype "unspecified"))
      (node (ref "USB5") (pin "B2") (pinfunction "SSTXp2_B2") (pintype "unspecified"))
      (node (ref "USB6") (pin "A2") (pinfunction "SSTXP1_A2") (pintype "unspecified"))
      (node (ref "USB6") (pin "B2") (pinfunction "SSTXp2_B2") (pintype "unspecified"))
      (node (ref "USB7") (pin "A2") (pinfunction "SSTXP1_A2") (pintype "unspecified"))
      (node (ref "USB7") (pin "B2") (pinfunction "SSTXp2_B2") (pintype "unspecified"))
      (node (ref "USB8") (pin "A2") (pinfunction "SSTXP1_A2") (pintype "unspecified"))
      (node (ref "USB8") (pin "B2") (pinfunction "SSTXp2_B2") (pintype "unspecified"))
      (node (ref "USB9") (pin "A2") (pinfunction "SSTXP1_A2") (pintype "unspecified"))
      (node (ref "USB9") (pin "B2") (pinfunction "SSTXp2_B2") (pintype "unspecified"))
    )
    (net (code "23") (name "/VCC3_3V") (class "Default")
      (node (ref "USB1") (pin "A10") (pinfunction "SSRXn2_A10") (pintype "unspecified"))
      (node (ref "USB1") (pin "B10") (pinfunction "SSRXn1_B10") (pintype "unspecified"))
      (node (ref "USB10") (pin "A10") (pinfunction "SSRXn2_A10") (pintype "unspecified"))
      (node (ref "USB10") (pin "B10") (pinfunction "SSRXn1_B10") (pintype "unspecified"))
      (node (ref "USB11") (pin "A10") (pinfunction "SSRXn2_A10") (pintype "unspecified"))
      (node (ref "USB11") (pin "B10") (pinfunction "SSRXn1_B10") (pintype "unspecified"))
      (node (ref "USB12") (pin "A10") (pinfunction "SSRXn2_A10") (pintype "unspecified"))
      (node (ref "USB12") (pin "B10") (pinfunction "SSRXn1_B10") (pintype "unspecified"))
      (node (ref "USB13") (pin "A10") (pinfunction "SSRXn2_A10") (pintype "unspecified"))
      (node (ref "USB13") (pin "B10") (pinfunction "SSRXn1_B10") (pintype "unspecified"))
      (node (ref "USB14") (pin "A10") (pinfunction "SSRXn2_A10") (pintype "unspecified"))
      (node (ref "USB14") (pin "B10") (pinfunction "SSRXn1_B10") (pintype "unspecified"))
      (node (ref "USB15") (pin "A10") (pinfunction "SSRXn2_A10") (pintype "unspecified"))
      (node (ref "USB15") (pin "B10") (pinfunction "SSRXn1_B10") (pintype "unspecified"))
      (node (ref "USB16") (pin "A10") (pinfunction "SSRXn2_A10") (pintype "unspecified"))
      (node (ref "USB16") (pin "B10") (pinfunction "SSRXn1_B10") (pintype "unspecified"))
      (node (ref "USB2") (pin "A10") (pinfunction "SSRXn2_A10") (pintype "unspecified"))
      (node (ref "USB2") (pin "B10") (pinfunction "SSRXn1_B10") (pintype "unspecified"))
      (node (ref "USB3") (pin "A10") (pinfunction "SSRXn2_A10") (pintype "unspecified"))
      (node (ref "USB3") (pin "B10") (pinfunction "SSRXn1_B10") (pintype "unspecified"))
      (node (ref "USB4") (pin "A10") (pinfunction "SSRXn2_A10") (pintype "unspecified"))
      (node (ref "USB4") (pin "B10") (pinfunction "SSRXn1_B10") (pintype "unspecified"))
      (node (ref "USB5") (pin "A10") (pinfunction "SSRXn2_A10") (pintype "unspecified"))
      (node (ref "USB5") (pin "B10") (pinfunction "SSRXn1_B10") (pintype "unspecified"))
      (node (ref "USB6") (pin "A10") (pinfunction "SSRXn2_A10") (pintype "unspecified"))
      (node (ref "USB6") (pin "B10") (pinfunction "SSRXn1_B10") (pintype "unspecified"))
      (node (ref "USB7") (pin "A10") (pinfunction "SSRXn2_A10") (pintype "unspecified"))
      (node (ref "USB7") (pin "B10") (pinfunction "SSRXn1_B10") (pintype "unspecified"))
      (node (ref "USB8") (pin "A10") (pinfunction "SSRXn2_A10") (pintype "unspecified"))
      (node (ref "USB8") (pin "B10") (pinfunction "SSRXn1_B10") (pintype "unspecified"))
      (node (ref "USB9") (pin "A10") (pinfunction "SSRXn2_A10") (pintype "unspecified"))
      (node (ref "USB9") (pin "B10") (pinfunction "SSRXn1_B10") (pintype "unspecified"))
    )
    (net (code "24") (name "/VIN") (class "Default")
      (node (ref "CN1") (pin "2") (pinfunction "+_2") (pintype "unspecified"))
      (node (ref "USB1") (pin "A4") (pinfunction "VBUS_A4") (pintype "unspecified"))
      (node (ref "USB1") (pin "A9") (pinfunction "VBUS_A9") (pintype "unspecified"))
      (node (ref "USB1") (pin "B4") (pinfunction "VBUS_B4") (pintype "unspecified"))
      (node (ref "USB1") (pin "B9") (pinfunction "VBUS_B9") (pintype "unspecified"))
      (node (ref "USB10") (pin "A4") (pinfunction "VBUS_A4") (pintype "unspecified"))
      (node (ref "USB10") (pin "A9") (pinfunction "VBUS_A9") (pintype "unspecified"))
      (node (ref "USB10") (pin "B4") (pinfunction "VBUS_B4") (pintype "unspecified"))
      (node (ref "USB10") (pin "B9") (pinfunction "VBUS_B9") (pintype "unspecified"))
      (node (ref "USB11") (pin "A4") (pinfunction "VBUS_A4") (pintype "unspecified"))
      (node (ref "USB11") (pin "A9") (pinfunction "VBUS_A9") (pintype "unspecified"))
      (node (ref "USB11") (pin "B4") (pinfunction "VBUS_B4") (pintype "unspecified"))
      (node (ref "USB11") (pin "B9") (pinfunction "VBUS_B9") (pintype "unspecified"))
      (node (ref "USB12") (pin "A4") (pinfunction "VBUS_A4") (pintype "unspecified"))
      (node (ref "USB12") (pin "A9") (pinfunction "VBUS_A9") (pintype "unspecified"))
      (node (ref "USB12") (pin "B4") (pinfunction "VBUS_B4") (pintype "unspecified"))
      (node (ref "USB12") (pin "B9") (pinfunction "VBUS_B9") (pintype "unspecified"))
      (node (ref "USB13") (pin "A4") (pinfunction "VBUS_A4") (pintype "unspecified"))
      (node (ref "USB13") (pin "A9") (pinfunction "VBUS_A9") (pintype "unspecified"))
      (node (ref "USB13") (pin "B4") (pinfunction "VBUS_B4") (pintype "unspecified"))
      (node (ref "USB13") (pin "B9") (pinfunction "VBUS_B9") (pintype "unspecified"))
      (node (ref "USB14") (pin "A4") (pinfunction "VBUS_A4") (pintype "unspecified"))
      (node (ref "USB14") (pin "A9") (pinfunction "VBUS_A9") (pintype "unspecified"))
      (node (ref "USB14") (pin "B4") (pinfunction "VBUS_B4") (pintype "unspecified"))
      (node (ref "USB14") (pin "B9") (pinfunction "VBUS_B9") (pintype "unspecified"))
      (node (ref "USB15") (pin "A4") (pinfunction "VBUS_A4") (pintype "unspecified"))
      (node (ref "USB15") (pin "A9") (pinfunction "VBUS_A9") (pintype "unspecified"))
      (node (ref "USB15") (pin "B4") (pinfunction "VBUS_B4") (pintype "unspecified"))
      (node (ref "USB15") (pin "B9") (pinfunction "VBUS_B9") (pintype "unspecified"))
      (node (ref "USB16") (pin "A4") (pinfunction "VBUS_A4") (pintype "unspecified"))
      (node (ref "USB16") (pin "A9") (pinfunction "VBUS_A9") (pintype "unspecified"))
      (node (ref "USB16") (pin "B4") (pinfunction "VBUS_B4") (pintype "unspecified"))
      (node (ref "USB16") (pin "B9") (pinfunction "VBUS_B9") (pintype "unspecified"))
      (node (ref "USB2") (pin "A4") (pinfunction "VBUS_A4") (pintype "unspecified"))
      (node (ref "USB2") (pin "A9") (pinfunction "VBUS_A9") (pintype "unspecified"))
      (node (ref "USB2") (pin "B4") (pinfunction "VBUS_B4") (pintype "unspecified"))
      (node (ref "USB2") (pin "B9") (pinfunction "VBUS_B9") (pintype "unspecified"))
      (node (ref "USB3") (pin "A4") (pinfunction "VBUS_A4") (pintype "unspecified"))
      (node (ref "USB3") (pin "A9") (pinfunction "VBUS_A9") (pintype "unspecified"))
      (node (ref "USB3") (pin "B4") (pinfunction "VBUS_B4") (pintype "unspecified"))
      (node (ref "USB3") (pin "B9") (pinfunction "VBUS_B9") (pintype "unspecified"))
      (node (ref "USB4") (pin "A4") (pinfunction "VBUS_A4") (pintype "unspecified"))
      (node (ref "USB4") (pin "A9") (pinfunction "VBUS_A9") (pintype "unspecified"))
      (node (ref "USB4") (pin "B4") (pinfunction "VBUS_B4") (pintype "unspecified"))
      (node (ref "USB4") (pin "B9") (pinfunction "VBUS_B9") (pintype "unspecified"))
      (node (ref "USB5") (pin "A4") (pinfunction "VBUS_A4") (pintype "unspecified"))
      (node (ref "USB5") (pin "A9") (pinfunction "VBUS_A9") (pintype "unspecified"))
      (node (ref "USB5") (pin "B4") (pinfunction "VBUS_B4") (pintype "unspecified"))
      (node (ref "USB5") (pin "B9") (pinfunction "VBUS_B9") (pintype "unspecified"))
      (node (ref "USB6") (pin "A4") (pinfunction "VBUS_A4") (pintype "unspecified"))
      (node (ref "USB6") (pin "A9") (pinfunction "VBUS_A9") (pintype "unspecified"))
      (node (ref "USB6") (pin "B4") (pinfunction "VBUS_B4") (pintype "unspecified"))
      (node (ref "USB6") (pin "B9") (pinfunction "VBUS_B9") (pintype "unspecified"))
      (node (ref "USB7") (pin "A4") (pinfunction "VBUS_A4") (pintype "unspecified"))
      (node (ref "USB7") (pin "A9") (pinfunction "VBUS_A9") (pintype "unspecified"))
      (node (ref "USB7") (pin "B4") (pinfunction "VBUS_B4") (pintype "unspecified"))
      (node (ref "USB7") (pin "B9") (pinfunction "VBUS_B9") (pintype "unspecified"))
      (node (ref "USB8") (pin "A4") (pinfunction "VBUS_A4") (pintype "unspecified"))
      (node (ref "USB8") (pin "A9") (pinfunction "VBUS_A9") (pintype "unspecified"))
      (node (ref "USB8") (pin "B4") (pinfunction "VBUS_B4") (pintype "unspecified"))
      (node (ref "USB8") (pin "B9") (pinfunction "VBUS_B9") (pintype "unspecified"))
      (node (ref "USB9") (pin "A4") (pinfunction "VBUS_A4") (pintype "unspecified"))
      (node (ref "USB9") (pin "A9") (pinfunction "VBUS_A9") (pintype "unspecified"))
      (node (ref "USB9") (pin "B4") (pinfunction "VBUS_B4") (pintype "unspecified"))
      (node (ref "USB9") (pin "B9") (pinfunction "VBUS_B9") (pintype "unspecified"))
    )
    (net (code "25") (name "GND") (class "Default")
      (node (ref "CN1") (pin "1") (pinfunction "-_1") (pintype "unspecified"))
      (node (ref "R1") (pin "2") (pinfunction "2_2") (pintype "input"))
      (node (ref "R10") (pin "2") (pinfunction "2_2") (pintype "input"))
      (node (ref "R11") (pin "2") (pinfunction "2_2") (pintype "input"))
      (node (ref "R12") (pin "2") (pinfunction "2_2") (pintype "input"))
      (node (ref "R13") (pin "2") (pinfunction "2_2") (pintype "input"))
      (node (ref "R14") (pin "2") (pinfunction "2_2") (pintype "input"))
      (node (ref "R15") (pin "2") (pinfunction "2_2") (pintype "input"))
      (node (ref "R16") (pin "2") (pinfunction "2_2") (pintype "input"))
      (node (ref "R2") (pin "2") (pinfunction "2_2") (pintype "input"))
      (node (ref "R3") (pin "2") (pinfunction "2_2") (pintype "input"))
      (node (ref "R4") (pin "2") (pinfunction "2_2") (pintype "input"))
      (node (ref "R5") (pin "2") (pinfunction "2_2") (pintype "input"))
      (node (ref "R6") (pin "2") (pinfunction "2_2") (pintype "input"))
      (node (ref "R7") (pin "2") (pinfunction "2_2") (pintype "input"))
      (node (ref "R8") (pin "2") (pinfunction "2_2") (pintype "input"))
      (node (ref "R9") (pin "2") (pinfunction "2_2") (pintype "input"))
      (node (ref "USB1") (pin "A1") (pinfunction "GND_A1") (pintype "unspecified"))
      (node (ref "USB1") (pin "A12") (pinfunction "GND_A12") (pintype "unspecified"))
      (node (ref "USB1") (pin "B1") (pinfunction "GND_B1") (pintype "unspecified"))
      (node (ref "USB1") (pin "B12") (pinfunction "GND_B12") (pintype "unspecified"))
      (node (ref "USB10") (pin "A1") (pinfunction "GND_A1") (pintype "unspecified"))
      (node (ref "USB10") (pin "A12") (pinfunction "GND_A12") (pintype "unspecified"))
      (node (ref "USB10") (pin "B1") (pinfunction "GND_B1") (pintype "unspecified"))
      (node (ref "USB10") (pin "B12") (pinfunction "GND_B12") (pintype "unspecified"))
      (node (ref "USB11") (pin "A1") (pinfunction "GND_A1") (pintype "unspecified"))
      (node (ref "USB11") (pin "A12") (pinfunction "GND_A12") (pintype "unspecified"))
      (node (ref "USB11") (pin "B1") (pinfunction "GND_B1") (pintype "unspecified"))
      (node (ref "USB11") (pin "B12") (pinfunction "GND_B12") (pintype "unspecified"))
      (node (ref "USB12") (pin "A1") (pinfunction "GND_A1") (pintype "unspecified"))
      (node (ref "USB12") (pin "A12") (pinfunction "GND_A12") (pintype "unspecified"))
      (node (ref "USB12") (pin "B1") (pinfunction "GND_B1") (pintype "unspecified"))
      (node (ref "USB12") (pin "B12") (pinfunction "GND_B12") (pintype "unspecified"))
      (node (ref "USB13") (pin "A1") (pinfunction "GND_A1") (pintype "unspecified"))
      (node (ref "USB13") (pin "A12") (pinfunction "GND_A12") (pintype "unspecified"))
      (node (ref "USB13") (pin "B1") (pinfunction "GND_B1") (pintype "unspecified"))
      (node (ref "USB13") (pin "B12") (pinfunction "GND_B12") (pintype "unspecified"))
      (node (ref "USB14") (pin "A1") (pinfunction "GND_A1") (pintype "unspecified"))
      (node (ref "USB14") (pin "A12") (pinfunction "GND_A12") (pintype "unspecified"))
      (node (ref "USB14") (pin "B1") (pinfunction "GND_B1") (pintype "unspecified"))
      (node (ref "USB14") (pin "B12") (pinfunction "GND_B12") (pintype "unspecified"))
      (node (ref "USB15") (pin "A1") (pinfunction "GND_A1") (pintype "unspecified"))
      (node (ref "USB15") (pin "A12") (pinfunction "GND_A12") (pintype "unspecified"))
      (node (ref "USB15") (pin "B1") (pinfunction "GND_B1") (pintype "unspecified"))
      (node (ref "USB15") (pin "B12") (pinfunction "GND_B12") (pintype "unspecified"))
      (node (ref "USB16") (pin "A1") (pinfunction "GND_A1") (pintype "unspecified"))
      (node (ref "USB16") (pin "A12") (pinfunction "GND_A12") (pintype "unspecified"))
      (node (ref "USB16") (pin "B1") (pinfunction "GND_B1") (pintype "unspecified"))
      (node (ref "USB16") (pin "B12") (pinfunction "GND_B12") (pintype "unspecified"))
      (node (ref "USB2") (pin "A1") (pinfunction "GND_A1") (pintype "unspecified"))
      (node (ref "USB2") (pin "A12") (pinfunction "GND_A12") (pintype "unspecified"))
      (node (ref "USB2") (pin "B1") (pinfunction "GND_B1") (pintype "unspecified"))
      (node (ref "USB2") (pin "B12") (pinfunction "GND_B12") (pintype "unspecified"))
      (node (ref "USB3") (pin "A1") (pinfunction "GND_A1") (pintype "unspecified"))
      (node (ref "USB3") (pin "A12") (pinfunction "GND_A12") (pintype "unspecified"))
      (node (ref "USB3") (pin "B1") (pinfunction "GND_B1") (pintype "unspecified"))
      (node (ref "USB3") (pin "B12") (pinfunction "GND_B12") (pintype "unspecified"))
      (node (ref "USB4") (pin "A1") (pinfunction "GND_A1") (pintype "unspecified"))
      (node (ref "USB4") (pin "A12") (pinfunction "GND_A12") (pintype "unspecified"))
      (node (ref "USB4") (pin "B1") (pinfunction "GND_B1") (pintype "unspecified"))
      (node (ref "USB4") (pin "B12") (pinfunction "GND_B12") (pintype "unspecified"))
      (node (ref "USB5") (pin "A1") (pinfunction "GND_A1") (pintype "unspecified"))
      (node (ref "USB5") (pin "A12") (pinfunction "GND_A12") (pintype "unspecified"))
      (node (ref "USB5") (pin "B1") (pinfunction "GND_B1") (pintype "unspecified"))
      (node (ref "USB5") (pin "B12") (pinfunction "GND_B12") (pintype "unspecified"))
      (node (ref "USB6") (pin "A1") (pinfunction "GND_A1") (pintype "unspecified"))
      (node (ref "USB6") (pin "A12") (pinfunction "GND_A12") (pintype "unspecified"))
      (node (ref "USB6") (pin "B1") (pinfunction "GND_B1") (pintype "unspecified"))
      (node (ref "USB6") (pin "B12") (pinfunction "GND_B12") (pintype "unspecified"))
      (node (ref "USB7") (pin "A1") (pinfunction "GND_A1") (pintype "unspecified"))
      (node (ref "USB7") (pin "A12") (pinfunction "GND_A12") (pintype "unspecified"))
      (node (ref "USB7") (pin "B1") (pinfunction "GND_B1") (pintype "unspecified"))
      (node (ref "USB7") (pin "B12") (pinfunction "GND_B12") (pintype "unspecified"))
      (node (ref "USB8") (pin "A1") (pinfunction "GND_A1") (pintype "unspecified"))
      (node (ref "USB8") (pin "A12") (pinfunction "GND_A12") (pintype "unspecified"))
      (node (ref "USB8") (pin "B1") (pinfunction "GND_B1") (pintype "unspecified"))
      (node (ref "USB8") (pin "B12") (pinfunction "GND_B12") (pintype "unspecified"))
      (node (ref "USB9") (pin "A1") (pinfunction "GND_A1") (pintype "unspecified"))
      (node (ref "USB9") (pin "A12") (pinfunction "GND_A12") (pintype "unspecified"))
      (node (ref "USB9") (pin "B1") (pinfunction "GND_B1") (pintype "unspecified"))
      (node (ref "USB9") (pin "B12") (pinfunction "GND_B12") (pintype "unspecified"))
    )
    (net (code "26") (name "Net-(LED1-C)") (class "Default")
      (node (ref "LED1") (pin "1") (pinfunction "C_1") (pintype "input"))
      (node (ref "R1") (pin "1") (pinfunction "1_1") (pintype "input"))
    )
    (net (code "27") (name "Net-(LED2-C)") (class "Default")
      (node (ref "LED2") (pin "1") (pinfunction "C_1") (pintype "input"))
      (node (ref "R2") (pin "1") (pinfunction "1_1") (pintype "input"))
    )
    (net (code "28") (name "Net-(LED3-C)") (class "Default")
      (node (ref "LED3") (pin "1") (pinfunction "C_1") (pintype "input"))
      (node (ref "R3") (pin "1") (pinfunction "1_1") (pintype "input"))
    )
    (net (code "29") (name "Net-(LED4-C)") (class "Default")
      (node (ref "LED4") (pin "1") (pinfunction "C_1") (pintype "input"))
      (node (ref "R4") (pin "1") (pinfunction "1_1") (pintype "input"))
    )
    (net (code "30") (name "Net-(LED5-C)") (class "Default")
      (node (ref "LED5") (pin "1") (pinfunction "C_1") (pintype "input"))
      (node (ref "R5") (pin "1") (pinfunction "1_1") (pintype "input"))
    )
    (net (code "31") (name "Net-(LED6-C)") (class "Default")
      (node (ref "LED6") (pin "1") (pinfunction "C_1") (pintype "input"))
      (node (ref "R6") (pin "1") (pinfunction "1_1") (pintype "input"))
    )
    (net (code "32") (name "Net-(LED7-C)") (class "Default")
      (node (ref "LED7") (pin "1") (pinfunction "C_1") (pintype "input"))
      (node (ref "R7") (pin "1") (pinfunction "1_1") (pintype "input"))
    )
    (net (code "33") (name "Net-(LED8-C)") (class "Default")
      (node (ref "LED8") (pin "1") (pinfunction "C_1") (pintype "input"))
      (node (ref "R8") (pin "1") (pinfunction "1_1") (pintype "input"))
    )
    (net (code "34") (name "Net-(LED9-C)") (class "Default")
      (node (ref "LED9") (pin "1") (pinfunction "C_1") (pintype "input"))
      (node (ref "R9") (pin "1") (pinfunction "1_1") (pintype "input"))
    )
    (net (code "35") (name "Net-(LED10-C)") (class "Default")
      (node (ref "LED10") (pin "1") (pinfunction "C_1") (pintype "input"))
      (node (ref "R10") (pin "1") (pinfunction "1_1") (pintype "input"))
    )
    (net (code "36") (name "Net-(LED11-C)") (class "Default")
      (node (ref "LED11") (pin "1") (pinfunction "C_1") (pintype "input"))
      (node (ref "R11") (pin "1") (pinfunction "1_1") (pintype "input"))
    )
    (net (code "37") (name "Net-(LED12-C)") (class "Default")
      (node (ref "LED12") (pin "1") (pinfunction "C_1") (pintype "input"))
      (node (ref "R12") (pin "1") (pinfunction "1_1") (pintype "input"))
    )
    (net (code "38") (name "Net-(LED13-C)") (class "Default")
      (node (ref "LED13") (pin "1") (pinfunction "C_1") (pintype "input"))
      (node (ref "R13") (pin "1") (pinfunction "1_1") (pintype "input"))
    )
    (net (code "39") (name "Net-(LED14-C)") (class "Default")
      (node (ref "LED14") (pin "1") (pinfunction "C_1") (pintype "input"))
      (node (ref "R14") (pin "1") (pinfunction "1_1") (pintype "input"))
    )
    (net (code "40") (name "Net-(LED15-C)") (class "Default")
      (node (ref "LED15") (pin "1") (pinfunction "C_1") (pintype "input"))
      (node (ref "R15") (pin "1") (pinfunction "1_1") (pintype "input"))
    )
    (net (code "41") (name "Net-(LED16-C)") (class "Default")
      (node (ref "LED16") (pin "1") (pinfunction "C_1") (pintype "input"))
      (node (ref "R16") (pin "1") (pinfunction "1_1") (pintype "input"))
    )
    (net (code "42") (name "unconnected-(CN1-Pad3)") (class "Default")
      (node (ref "CN1") (pin "3") (pinfunction "3_3") (pintype "unspecified+no_connect"))
    )
    (net (code "43") (name "unconnected-(CN1-Pad4)") (class "Default")
      (node (ref "CN1") (pin "4") (pinfunction "4_4") (pintype "unspecified+no_connect"))
    )
    (net (code "44") (name "unconnected-(USB1-EH-Pad25)") (class "Default")
      (node (ref "USB1") (pin "25") (pinfunction "EH_25") (pintype "unspecified+no_connect"))
    )
    (net (code "45") (name "unconnected-(USB2-EH-Pad25)") (class "Default")
      (node (ref "USB2") (pin "25") (pinfunction "EH_25") (pintype "unspecified+no_connect"))
    )
    (net (code "46") (name "unconnected-(USB3-EH-Pad25)") (class "Default")
      (node (ref "USB3") (pin "25") (pinfunction "EH_25") (pintype "unspecified+no_connect"))
    )
    (net (code "47") (name "unconnected-(USB4-EH-Pad25)") (class "Default")
      (node (ref "USB4") (pin "25") (pinfunction "EH_25") (pintype "unspecified+no_connect"))
    )
    (net (code "48") (name "unconnected-(USB5-EH-Pad25)") (class "Default")
      (node (ref "USB5") (pin "25") (pinfunction "EH_25") (pintype "unspecified+no_connect"))
    )
    (net (code "49") (name "unconnected-(USB6-EH-Pad25)") (class "Default")
      (node (ref "USB6") (pin "25") (pinfunction "EH_25") (pintype "unspecified+no_connect"))
    )
    (net (code "50") (name "unconnected-(USB7-EH-Pad25)") (class "Default")
      (node (ref "USB7") (pin "25") (pinfunction "EH_25") (pintype "unspecified+no_connect"))
    )
    (net (code "51") (name "unconnected-(USB8-EH-Pad25)") (class "Default")
      (node (ref "USB8") (pin "25") (pinfunction "EH_25") (pintype "unspecified+no_connect"))
    )
    (net (code "52") (name "unconnected-(USB9-EH-Pad25)") (class "Default")
      (node (ref "USB9") (pin "25") (pinfunction "EH_25") (pintype "unspecified+no_connect"))
    )
    (net (code "53") (name "unconnected-(USB10-EH-Pad25)") (class "Default")
      (node (ref "USB10") (pin "25") (pinfunction "EH_25") (pintype "unspecified+no_connect"))
    )
    (net (code "54") (name "unconnected-(USB11-EH-Pad25)") (class "Default")
      (node (ref "USB11") (pin "25") (pinfunction "EH_25") (pintype "unspecified+no_connect"))
    )
    (net (code "55") (name "unconnected-(USB12-EH-Pad25)") (class "Default")
      (node (ref "USB12") (pin "25") (pinfunction "EH_25") (pintype "unspecified+no_connect"))
    )
    (net (code "56") (name "unconnected-(USB13-EH-Pad25)") (class "Default")
      (node (ref "USB13") (pin "25") (pinfunction "EH_25") (pintype "unspecified+no_connect"))
    )
    (net (code "57") (name "unconnected-(USB14-EH-Pad25)") (class "Default")
      (node (ref "USB14") (pin "25") (pinfunction "EH_25") (pintype "unspecified+no_connect"))
    )
    (net (code "58") (name "unconnected-(USB15-EH-Pad25)") (class "Default")
      (node (ref "USB15") (pin "25") (pinfunction "EH_25") (pintype "unspecified+no_connect"))
    )
    (net (code "59") (name "unconnected-(USB16-EH-Pad25)") (class "Default")
      (node (ref "USB16") (pin "25") (pinfunction "EH_25") (pintype "unspecified+no_connect"))
    )
  )
)
